# Arduino_Uno.net
KiCad netlist of a schematic drawn in Altium Designer
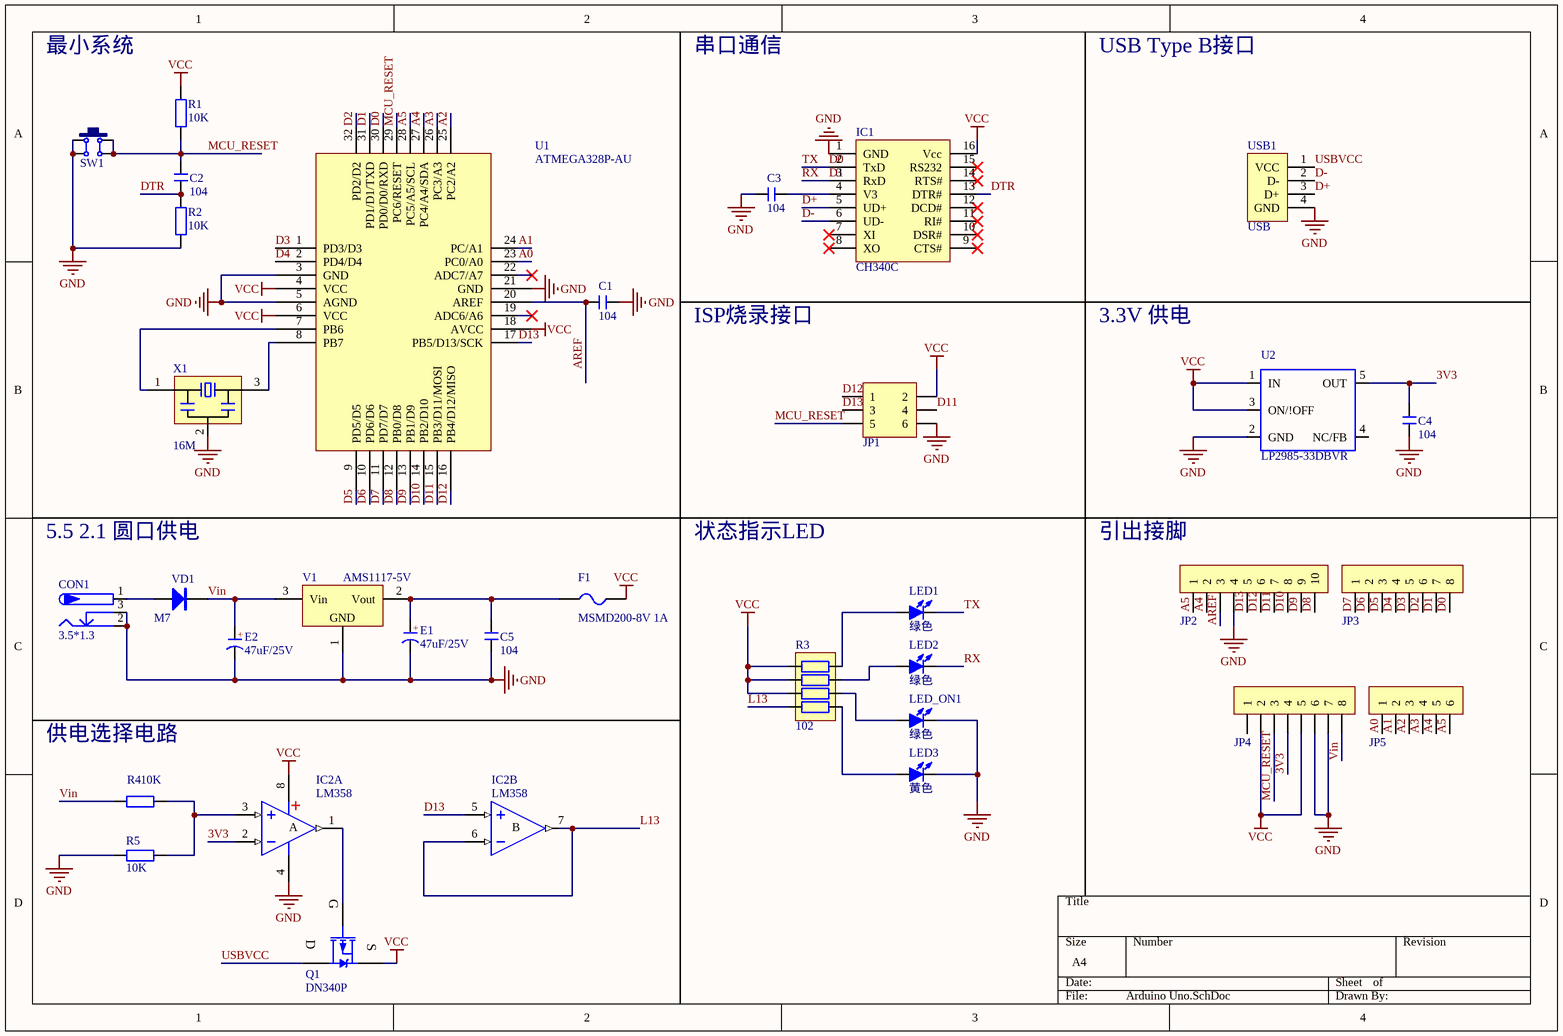
[diagram p0: Arduino Uno.SchDoc]

(export (version "E")
  (design (tool "Eeschema 10.0.6"))
  (components
    (comp (ref "C1")
      (value "104")
      (footprint "C 0603_L")
      (description "无极性贴片电容")
      (fields (field (name "版权归属") "源创客"))
      (libsource (lib "电阻-电容-电感") (part "C"))
    )
    (comp (ref "C2")
      (value "104")
      (footprint "C 0603_L")
      (description "无极性贴片电容")
      (fields (field (name "版权归属") "源创客"))
      (libsource (lib "电阻-电容-电感") (part "C"))
    )
    (comp (ref "C3")
      (value "104")
      (footprint "C 0603_L")
      (description "无极性贴片电容")
      (fields (field (name "版权归属") "源创客"))
      (libsource (lib "电阻-电容-电感") (part "C"))
    )
    (comp (ref "C4")
      (value "104")
      (footprint "C 0603_L")
      (description "无极性贴片电容")
      (fields (field (name "版权归属") "源创客"))
      (libsource (lib "电阻-电容-电感") (part "C"))
    )
    (comp (ref "C5")
      (value "104")
      (footprint "C 0603_L")
      (description "无极性贴片电容")
      (fields (field (name "版权归属") "源创客"))
      (libsource (lib "电阻-电容-电感") (part "C"))
    )
    (comp (ref "CON1")
      (value "3.5*1.3")
      (footprint "DC-005")
      (description "低压电源接口")
      (fields (field (name "版权归属") "源创客"))
      (libsource (lib "接口类") (part "P-DC"))
    )
    (comp (ref "E1")
      (value "47uF/25V")
      (footprint "CM D(6.3*5.4)")
      (description "贴片电解电容")
      (fields (field (name "版权归属") "源创客"))
      (libsource (lib "电阻-电容-电感") (part "C-CM"))
    )
    (comp (ref "E2")
      (value "47uF/25V")
      (footprint "CM D(6.3*5.4)")
      (description "贴片电解电容")
      (fields (field (name "版权归属") "源创客"))
      (libsource (lib "电阻-电容-电感") (part "C-CM"))
    )
    (comp (ref "F1")
      (value "MSMD200-8V 1A")
      (footprint "FU 1812")
      (description "贴片保险丝")
      (fields (field (name "版权归属") "源创客"))
      (libsource (lib "保险丝-晶振") (part "FU"))
    )
    (comp (ref "IC1")
      (value "CH340C")
      (footprint "SOP16_L")
      (description "串口转USB")
      (fields (field (name "版权归属") "源创客"))
      (libsource (lib "IC芯片") (part "CH340G"))
    )
    (comp (ref "IC2")
      (value "LM358")
      (footprint "MSOP8_L")
      (description "双路运放")
      (fields (field (name "版权归属") "源创客"))
      (libsource (lib "IC芯片") (part "LM358"))
    )
    (comp (ref "JP1")
      (value "Header3X2")
      (footprint "HDR2.54-LI-2x3P")
      (description "3*2P接插件")
      (fields (field (name "版权归属") "源创客"))
      (libsource (lib "接插件") (part "Header 3X2"))
    )
    (comp (ref "JP2")
      (value "HDR-1X10")
      (footprint "HDR2.54-M-LI-10P")
      (description "10P接插件")
      (fields (field (name "版权归属") "源创客"))
      (libsource (lib "接插件") (part "Header 10"))
    )
    (comp (ref "JP3")
      (value "HDR-1X8")
      (footprint "HDR2.54-M-LI-8P")
      (description "8P接插件")
      (fields (field (name "版权归属") "源创客"))
      (libsource (lib "接插件") (part "Header 8"))
    )
    (comp (ref "JP4")
      (value "HDR-1X8")
      (footprint "HDR2.54-M-LI-8P")
      (description "8P接插件")
      (fields (field (name "版权归属") "源创客"))
      (libsource (lib "接插件") (part "Header 8"))
    )
    (comp (ref "JP5")
      (value "HDR-1X6")
      (footprint "HDR2.54-M-LI-6P")
      (description "6P接插件")
      (fields (field (name "版权归属") "源创客"))
      (libsource (lib "接插件") (part "Header 6"))
    )
    (comp (ref "LED1")
      (value "绿色")
      (footprint "LED 0603B")
      (description "贴片LED")
      (fields (field (name "版权归属") "源创客"))
      (libsource (lib "LED") (part "LED-SMD"))
    )
    (comp (ref "LED2")
      (value "绿色")
      (footprint "LED 0603B")
      (description "贴片LED")
      (fields (field (name "版权归属") "源创客"))
      (libsource (lib "LED") (part "LED-SMD"))
    )
    (comp (ref "LED3")
      (value "黄色")
      (footprint "LED 0603B")
      (description "贴片LED")
      (fields (field (name "版权归属") "源创客"))
      (libsource (lib "LED") (part "LED-SMD"))
    )
    (comp (ref "LED_ON1")
      (value "绿色")
      (footprint "LED 0603B")
      (description "贴片LED")
      (fields (field (name "版权归属") "源创客"))
      (libsource (lib "LED") (part "LED-SMD"))
    )
    (comp (ref "Q1")
      (value "DN340P")
      (footprint "SOT23-3N")
      (description "P沟道场效应管")
      (fields (field (name "版权归属") "源创客"))
      (libsource (lib "场效应管-可控硅") (part "SI2301"))
    )
    (comp (ref "R1")
      (value "10K")
      (footprint "R 0603_L")
      (description "贴片电阻")
      (fields (field (name "版权归属") "源创客"))
      (libsource (lib "电阻-电容-电感") (part "R"))
    )
    (comp (ref "R2")
      (value "10K")
      (footprint "R 0603_L")
      (description "贴片电阻")
      (fields (field (name "版权归属") "源创客"))
      (libsource (lib "电阻-电容-电感") (part "R"))
    )
    (comp (ref "R3")
      (value "102")
      (footprint "RCA-8P4R-0603")
      (description "贴片网络排阻")
      (fields (field (name "版权归属") "源创客"))
      (libsource (lib "电阻-电容-电感") (part "R-8P4R"))
    )
    (comp (ref "R4")
      (value "10K")
      (footprint "R 0603_L")
      (description "贴片电阻")
      (fields (field (name "版权归属") "源创客"))
      (libsource (lib "电阻-电容-电感") (part "R"))
    )
    (comp (ref "R5")
      (value "10K")
      (footprint "R 0603_L")
      (description "贴片电阻")
      (fields (field (name "版权归属") "源创客"))
      (libsource (lib "电阻-电容-电感") (part "R"))
    )
    (comp (ref "SW1")
      (value "4x4x1.5")
      (footprint "TSW SMD-6*6*4.3")
      (description "防水轻触开关")
      (fields (field (name "版权归属") "源创客"))
      (libsource (lib "5.1   - 按键-开关") (part "TS-030"))
    )
    (comp (ref "U1")
      (value "ATMEGA328P-AU")
      (footprint "LQFP32 7X7_L")
      (description "AVR单片机")
      (fields (field (name "版权归属") "源创客"))
      (libsource (lib "Atmel系列单片机") (part "ATMEGA328P"))
    )
    (comp (ref "U2")
      (value "LP2985-33DBVR")
      (footprint "SOT23-5L")
      (libsource (lib "*") (part "LP2985-XXDBVR33"))
    )
    (comp (ref "USB1")
      (value "USB")
      (footprint "USB-B/S_A")
      (description "USB-B型母接口")
      (fields (field (name "版权归属") "源创客"))
      (libsource (lib "接口类") (part "USB-B/S"))
    )
    (comp (ref "V1")
      (value "AMS1117-5V")
      (footprint "SOT223_N")
      (description "三端稳压芯片")
      (fields (field (name "版权归属") "源创客"))
      (libsource (lib "IC芯片") (part "AMS1117"))
    )
    (comp (ref "VD1")
      (value "M7")
      (footprint "SMA")
      (description "整流二极管")
      (fields (field (name "版权归属") "源创客"))
      (libsource (lib "二极管-整流桥") (part "M7"))
    )
    (comp (ref "X1")
      (value "16M")
      (footprint "OSC-3.2-1.3-3P")
      (description "3脚晶振")
      (fields (field (name "版权归属") "源创客"))
      (libsource (lib "保险丝-晶振") (part "XTAL-3"))
    )
  )
  (nets
    (net (code "1") (name "/3V3") (class "Default")
      (node (ref "C4") (pin "2") (pinfunction "2_2") (pintype "passive"))
      (node (ref "IC2") (pin "2") (pinfunction "IN-_2") (pintype "input"))
      (node (ref "JP4") (pin "4") (pinfunction "4_4") (pintype "passive"))
      (node (ref "U2") (pin "5") (pinfunction "OUT_5") (pintype "passive"))
    )
    (net (code "2") (name "/A0") (class "Default")
      (node (ref "JP5") (pin "1") (pinfunction "1_1") (pintype "passive"))
      (node (ref "U1") (pin "23") (pinfunction "PC0/A0_23") (pintype "passive"))
    )
    (net (code "3") (name "/A1") (class "Default")
      (node (ref "JP5") (pin "2") (pinfunction "2_2") (pintype "passive"))
      (node (ref "U1") (pin "24") (pinfunction "PC/A1_24") (pintype "passive"))
    )
    (net (code "4") (name "/A2") (class "Default")
      (node (ref "JP5") (pin "3") (pinfunction "3_3") (pintype "passive"))
      (node (ref "U1") (pin "25") (pinfunction "PC2/A2_25") (pintype "passive"))
    )
    (net (code "5") (name "/A3") (class "Default")
      (node (ref "JP5") (pin "4") (pinfunction "4_4") (pintype "passive"))
      (node (ref "U1") (pin "26") (pinfunction "PC3/A3_26") (pintype "passive"))
    )
    (net (code "6") (name "/A4") (class "Default")
      (node (ref "JP2") (pin "2") (pinfunction "2_2") (pintype "passive"))
      (node (ref "JP5") (pin "5") (pinfunction "5_5") (pintype "passive"))
      (node (ref "U1") (pin "27") (pinfunction "PC4/A4/SDA_27") (pintype "passive"))
    )
    (net (code "7") (name "/A5") (class "Default")
      (node (ref "JP2") (pin "1") (pinfunction "1_1") (pintype "passive"))
      (node (ref "JP5") (pin "6") (pinfunction "6_6") (pintype "passive"))
      (node (ref "U1") (pin "28") (pinfunction "PC5/A5/SCL_28") (pintype "passive"))
    )
    (net (code "8") (name "/AREF") (class "Default")
      (node (ref "C1") (pin "1") (pinfunction "1_1") (pintype "passive"))
      (node (ref "JP2") (pin "3") (pinfunction "3_3") (pintype "passive"))
      (node (ref "U1") (pin "20") (pinfunction "AREF_20") (pintype "passive"))
    )
    (net (code "9") (name "/D+") (class "Default")
      (node (ref "IC1") (pin "5") (pinfunction "UD+_5") (pintype "passive"))
      (node (ref "USB1") (pin "3") (pinfunction "D+_3") (pintype "passive"))
    )
    (net (code "10") (name "/D-") (class "Default")
      (node (ref "IC1") (pin "6") (pinfunction "UD-_6") (pintype "passive"))
      (node (ref "USB1") (pin "2") (pinfunction "D-_2") (pintype "passive"))
    )
    (net (code "11") (name "/D0") (class "Default")
      (node (ref "IC1") (pin "2") (pinfunction "TxD_2") (pintype "passive"))
      (node (ref "JP3") (pin "8") (pinfunction "8_8") (pintype "passive"))
      (node (ref "LED1") (pin "2") (pinfunction "K_2") (pintype "passive"))
      (node (ref "U1") (pin "30") (pinfunction "PD0/D0/RXD_30") (pintype "passive"))
    )
    (net (code "12") (name "/D1") (class "Default")
      (node (ref "IC1") (pin "3") (pinfunction "RxD_3") (pintype "passive"))
      (node (ref "JP3") (pin "7") (pinfunction "7_7") (pintype "passive"))
      (node (ref "LED2") (pin "2") (pinfunction "K_2") (pintype "passive"))
      (node (ref "U1") (pin "31") (pinfunction "PD1/D1/TXD_31") (pintype "passive"))
    )
    (net (code "13") (name "/D2") (class "Default")
      (node (ref "JP3") (pin "6") (pinfunction "6_6") (pintype "passive"))
      (node (ref "U1") (pin "32") (pinfunction "PD2/D2_32") (pintype "passive"))
    )
    (net (code "14") (name "/D3") (class "Default")
      (node (ref "JP3") (pin "5") (pinfunction "5_5") (pintype "passive"))
      (node (ref "U1") (pin "1") (pinfunction "PD3/D3_1") (pintype "passive"))
    )
    (net (code "15") (name "/D4") (class "Default")
      (node (ref "JP3") (pin "4") (pinfunction "4_4") (pintype "passive"))
      (node (ref "U1") (pin "2") (pinfunction "PD4/D4_2") (pintype "passive"))
    )
    (net (code "16") (name "/D5") (class "Default")
      (node (ref "JP3") (pin "3") (pinfunction "3_3") (pintype "passive"))
      (node (ref "U1") (pin "9") (pinfunction "PD5/D5_9") (pintype "passive"))
    )
    (net (code "17") (name "/D6") (class "Default")
      (node (ref "JP3") (pin "2") (pinfunction "2_2") (pintype "passive"))
      (node (ref "U1") (pin "10") (pinfunction "PD6/D6_10") (pintype "passive"))
    )
    (net (code "18") (name "/D7") (class "Default")
      (node (ref "JP3") (pin "1") (pinfunction "1_1") (pintype "passive"))
      (node (ref "U1") (pin "11") (pinfunction "PD7/D7_11") (pintype "passive"))
    )
    (net (code "19") (name "/D8") (class "Default")
      (node (ref "JP2") (pin "10") (pinfunction "10_10") (pintype "passive"))
      (node (ref "U1") (pin "12") (pinfunction "PB0/D8_12") (pintype "passive"))
    )
    (net (code "20") (name "/D9") (class "Default")
      (node (ref "JP2") (pin "9") (pinfunction "9_9") (pintype "passive"))
      (node (ref "U1") (pin "13") (pinfunction "PB1/D9_13") (pintype "passive"))
    )
    (net (code "21") (name "/D10") (class "Default")
      (node (ref "JP2") (pin "8") (pinfunction "8_8") (pintype "passive"))
      (node (ref "U1") (pin "14") (pinfunction "PB2/D10_14") (pintype "passive"))
    )
    (net (code "22") (name "/D11") (class "Default")
      (node (ref "JP1") (pin "4") (pinfunction "4_4") (pintype "passive"))
      (node (ref "JP2") (pin "7") (pinfunction "7_7") (pintype "passive"))
      (node (ref "U1") (pin "15") (pinfunction "PB3/D11/MOSI_15") (pintype "passive"))
    )
    (net (code "23") (name "/D12") (class "Default")
      (node (ref "JP1") (pin "1") (pinfunction "1_1") (pintype "passive"))
      (node (ref "JP2") (pin "6") (pinfunction "6_6") (pintype "passive"))
      (node (ref "U1") (pin "16") (pinfunction "PB4/D12/MISO_16") (pintype "passive"))
    )
    (net (code "24") (name "/D13") (class "Default")
      (node (ref "IC2") (pin "5") (pinfunction "IN+_5") (pintype "input"))
      (node (ref "JP1") (pin "3") (pinfunction "3_3") (pintype "passive"))
      (node (ref "JP2") (pin "5") (pinfunction "5_5") (pintype "passive"))
      (node (ref "U1") (pin "17") (pinfunction "PB5/D13/SCK_17") (pintype "passive"))
    )
    (net (code "25") (name "/DTR") (class "Default")
      (node (ref "C2") (pin "1") (pinfunction "1_1") (pintype "passive"))
      (node (ref "IC1") (pin "13") (pinfunction "DTR#_13") (pintype "passive"))
      (node (ref "R2") (pin "2") (pinfunction "2_2") (pintype "passive"))
    )
    (net (code "26") (name "/L13") (class "Default")
      (node (ref "IC2") (pin "6") (pinfunction "IN-_6") (pintype "input"))
      (node (ref "IC2") (pin "7") (pinfunction "OUT_7") (pintype "output"))
      (node (ref "R3") (pin "4") (pinfunction "4_4") (pintype "passive"))
    )
    (net (code "27") (name "/MCU_RESET") (class "Default")
      (node (ref "C2") (pin "2") (pinfunction "2_2") (pintype "passive"))
      (node (ref "JP1") (pin "5") (pinfunction "5_5") (pintype "passive"))
      (node (ref "JP4") (pin "3") (pinfunction "3_3") (pintype "passive"))
      (node (ref "R1") (pin "2") (pinfunction "2_2") (pintype "passive"))
      (node (ref "SW1") (pin "2") (pinfunction "2_2") (pintype "passive"))
      (node (ref "SW1") (pin "3") (pinfunction "3_3") (pintype "passive"))
      (node (ref "U1") (pin "29") (pinfunction "PC6/RESET_29") (pintype "passive"))
    )
    (net (code "28") (name "/USBVCC") (class "Default")
      (node (ref "Q1") (pin "3") (pinfunction "D_3") (pintype "passive"))
      (node (ref "USB1") (pin "1") (pinfunction "VCC_1") (pintype "passive"))
    )
    (net (code "29") (name "/Vin") (class "Default")
      (node (ref "E2") (pin "1") (pinfunction "A_1") (pintype "passive"))
      (node (ref "JP4") (pin "8") (pinfunction "8_8") (pintype "passive"))
      (node (ref "R4") (pin "2") (pinfunction "2_2") (pintype "passive"))
      (node (ref "V1") (pin "3") (pinfunction "Vin_3") (pintype "passive"))
      (node (ref "VD1") (pin "2") (pinfunction "K_2") (pintype "passive"))
    )
    (net (code "30") (name "GND") (class "Default")
      (node (ref "C1") (pin "2") (pinfunction "2_2") (pintype "passive"))
      (node (ref "C3") (pin "1") (pinfunction "1_1") (pintype "passive"))
      (node (ref "C4") (pin "1") (pinfunction "1_1") (pintype "passive"))
      (node (ref "C5") (pin "1") (pinfunction "1_1") (pintype "passive"))
      (node (ref "CON1") (pin "2") (pintype "power_in"))
      (node (ref "CON1") (pin "3") (pintype "power_in"))
      (node (ref "E1") (pin "2") (pinfunction "K_2") (pintype "passive"))
      (node (ref "E2") (pin "2") (pinfunction "K_2") (pintype "passive"))
      (node (ref "IC1") (pin "1") (pinfunction "GND_1") (pintype "passive"))
      (node (ref "IC2") (pin "4") (pinfunction "V-_4") (pintype "power_in"))
      (node (ref "JP1") (pin "6") (pinfunction "6_6") (pintype "passive"))
      (node (ref "JP2") (pin "4") (pinfunction "4_4") (pintype "passive"))
      (node (ref "JP4") (pin "6") (pinfunction "6_6") (pintype "passive"))
      (node (ref "JP4") (pin "7") (pinfunction "7_7") (pintype "passive"))
      (node (ref "LED3") (pin "2") (pinfunction "K_2") (pintype "passive"))
      (node (ref "LED_ON1") (pin "2") (pinfunction "K_2") (pintype "passive"))
      (node (ref "R2") (pin "1") (pinfunction "1_1") (pintype "passive"))
      (node (ref "R5") (pin "2") (pinfunction "2_2") (pintype "passive"))
      (node (ref "SW1") (pin "1") (pinfunction "1_1") (pintype "passive"))
      (node (ref "SW1") (pin "4") (pinfunction "4_4") (pintype "passive"))
      (node (ref "U1") (pin "21") (pinfunction "GND_21") (pintype "passive"))
      (node (ref "U1") (pin "3") (pinfunction "GND_3") (pintype "passive"))
      (node (ref "U1") (pin "5") (pinfunction "AGND_5") (pintype "passive"))
      (node (ref "U2") (pin "2") (pinfunction "GND_2") (pintype "passive"))
      (node (ref "USB1") (pin "4") (pinfunction "GND_4") (pintype "passive"))
      (node (ref "V1") (pin "1") (pinfunction "GND_1") (pintype "passive"))
      (node (ref "X1") (pin "2") (pinfunction "2_2") (pintype "passive"))
    )
    (net (code "31") (name "Net-(E1-A)") (class "Default")
      (node (ref "C5") (pin "2") (pinfunction "2_2") (pintype "passive"))
      (node (ref "E1") (pin "1") (pinfunction "A_1") (pintype "passive"))
      (node (ref "F1") (pin "1") (pinfunction "1_1") (pintype "passive"))
      (node (ref "V1") (pin "2") (pinfunction "Vout_2") (pintype "passive"))
    )
    (net (code "32") (name "Net-(IC1-V3)") (class "Default")
      (node (ref "C3") (pin "2") (pinfunction "2_2") (pintype "passive"))
      (node (ref "IC1") (pin "4") (pinfunction "V3_4") (pintype "passive"))
    )
    (net (code "33") (name "Net-(IC2A-IN+)") (class "Default")
      (node (ref "IC2") (pin "3") (pinfunction "IN+_3") (pintype "input"))
      (node (ref "R4") (pin "1") (pinfunction "1_1") (pintype "passive"))
      (node (ref "R5") (pin "1") (pinfunction "1_1") (pintype "passive"))
    )
    (net (code "34") (name "Net-(IC2A-OUT)") (class "Default")
      (node (ref "IC2") (pin "1") (pinfunction "OUT_1") (pintype "output"))
      (node (ref "Q1") (pin "1") (pinfunction "G_1") (pintype "passive"))
    )
    (net (code "35") (name "Net-(LED1-A)") (class "Default")
      (node (ref "LED1") (pin "1") (pinfunction "A_1") (pintype "passive"))
      (node (ref "R3") (pin "8") (pinfunction "8_8") (pintype "passive"))
    )
    (net (code "36") (name "Net-(LED2-A)") (class "Default")
      (node (ref "LED2") (pin "1") (pinfunction "A_1") (pintype "passive"))
      (node (ref "R3") (pin "7") (pinfunction "7_7") (pintype "passive"))
    )
    (net (code "37") (name "Net-(LED3-A)") (class "Default")
      (node (ref "LED3") (pin "1") (pinfunction "A_1") (pintype "passive"))
      (node (ref "R3") (pin "5") (pinfunction "5_5") (pintype "passive"))
    )
    (net (code "38") (name "Net-(LED_ON1-A)") (class "Default")
      (node (ref "LED_ON1") (pin "1") (pinfunction "A_1") (pintype "passive"))
      (node (ref "R3") (pin "6") (pinfunction "6_6") (pintype "passive"))
    )
    (net (code "39") (name "Net-(U1-PB6)") (class "Default")
      (node (ref "U1") (pin "7") (pinfunction "PB6_7") (pintype "passive"))
      (node (ref "X1") (pin "1") (pinfunction "1_1") (pintype "passive"))
    )
    (net (code "40") (name "Net-(U1-PB7)") (class "Default")
      (node (ref "U1") (pin "8") (pinfunction "PB7_8") (pintype "passive"))
      (node (ref "X1") (pin "3") (pinfunction "3_3") (pintype "passive"))
    )
    (net (code "41") (name "Net-(VD1-A)") (class "Default")
      (node (ref "CON1") (pin "1") (pintype "power_in"))
      (node (ref "VD1") (pin "1") (pinfunction "A_1") (pintype "passive"))
    )
    (net (code "42") (name "VCC") (class "Default")
      (node (ref "F1") (pin "2") (pinfunction "2_2") (pintype "passive"))
      (node (ref "IC1") (pin "16") (pinfunction "Vcc_16") (pintype "passive"))
      (node (ref "IC2") (pin "8") (pinfunction "V+_8") (pintype "power_in"))
      (node (ref "JP1") (pin "2") (pinfunction "2_2") (pintype "passive"))
      (node (ref "JP4") (pin "2") (pinfunction "2_2") (pintype "passive"))
      (node (ref "JP4") (pin "5") (pinfunction "5_5") (pintype "passive"))
      (node (ref "Q1") (pin "2") (pinfunction "S_2") (pintype "passive"))
      (node (ref "R1") (pin "1") (pinfunction "1_1") (pintype "passive"))
      (node (ref "R3") (pin "1") (pinfunction "1_1") (pintype "passive"))
      (node (ref "R3") (pin "2") (pinfunction "2_2") (pintype "passive"))
      (node (ref "R3") (pin "3") (pinfunction "3_3") (pintype "passive"))
      (node (ref "U1") (pin "18") (pinfunction "AVCC_18") (pintype "passive"))
      (node (ref "U1") (pin "4") (pinfunction "VCC_4") (pintype "passive"))
      (node (ref "U1") (pin "6") (pinfunction "VCC_6") (pintype "passive"))
      (node (ref "U2") (pin "1") (pinfunction "IN_1") (pintype "passive"))
      (node (ref "U2") (pin "3") (pinfunction "ON/!OFF_3") (pintype "passive"))
    )
    (net (code "43") (name "unconnected-(IC1-CTS#-Pad9)") (class "Default")
      (node (ref "IC1") (pin "9") (pinfunction "CTS#_9") (pintype "passive+no_connect"))
    )
    (net (code "44") (name "unconnected-(IC1-DCD#-Pad12)") (class "Default")
      (node (ref "IC1") (pin "12") (pinfunction "DCD#_12") (pintype "passive+no_connect"))
    )
    (net (code "45") (name "unconnected-(IC1-DSR#-Pad10)") (class "Default")
      (node (ref "IC1") (pin "10") (pinfunction "DSR#_10") (pintype "passive+no_connect"))
    )
    (net (code "46") (name "unconnected-(IC1-RI#-Pad11)") (class "Default")
      (node (ref "IC1") (pin "11") (pinfunction "RI#_11") (pintype "passive+no_connect"))
    )
    (net (code "47") (name "unconnected-(IC1-RS232-Pad15)") (class "Default")
      (node (ref "IC1") (pin "15") (pinfunction "RS232_15") (pintype "passive+no_connect"))
    )
    (net (code "48") (name "unconnected-(IC1-RTS#-Pad14)") (class "Default")
      (node (ref "IC1") (pin "14") (pinfunction "RTS#_14") (pintype "passive+no_connect"))
    )
    (net (code "49") (name "unconnected-(IC1-XI-Pad7)") (class "Default")
      (node (ref "IC1") (pin "7") (pinfunction "XI_7") (pintype "passive+no_connect"))
    )
    (net (code "50") (name "unconnected-(IC1-XO-Pad8)") (class "Default")
      (node (ref "IC1") (pin "8") (pinfunction "XO_8") (pintype "passive+no_connect"))
    )
    (net (code "51") (name "unconnected-(JP4-Pad1)") (class "Default")
      (node (ref "JP4") (pin "1") (pinfunction "1_1") (pintype "passive"))
    )
    (net (code "52") (name "unconnected-(U1-ADC6{slash}A6-Pad19)") (class "Default")
      (node (ref "U1") (pin "19") (pinfunction "ADC6/A6_19") (pintype "passive+no_connect"))
    )
    (net (code "53") (name "unconnected-(U1-ADC7{slash}A7-Pad22)") (class "Default")
      (node (ref "U1") (pin "22") (pinfunction "ADC7/A7_22") (pintype "passive+no_connect"))
    )
    (net (code "54") (name "unconnected-(U2-NC{slash}FB-Pad4)") (class "Default")
      (node (ref "U2") (pin "4") (pinfunction "NC/FB_4") (pintype "passive"))
    )
  )
)
